# untitled.net
KiCad netlist of a schematic drawn in EAGLE
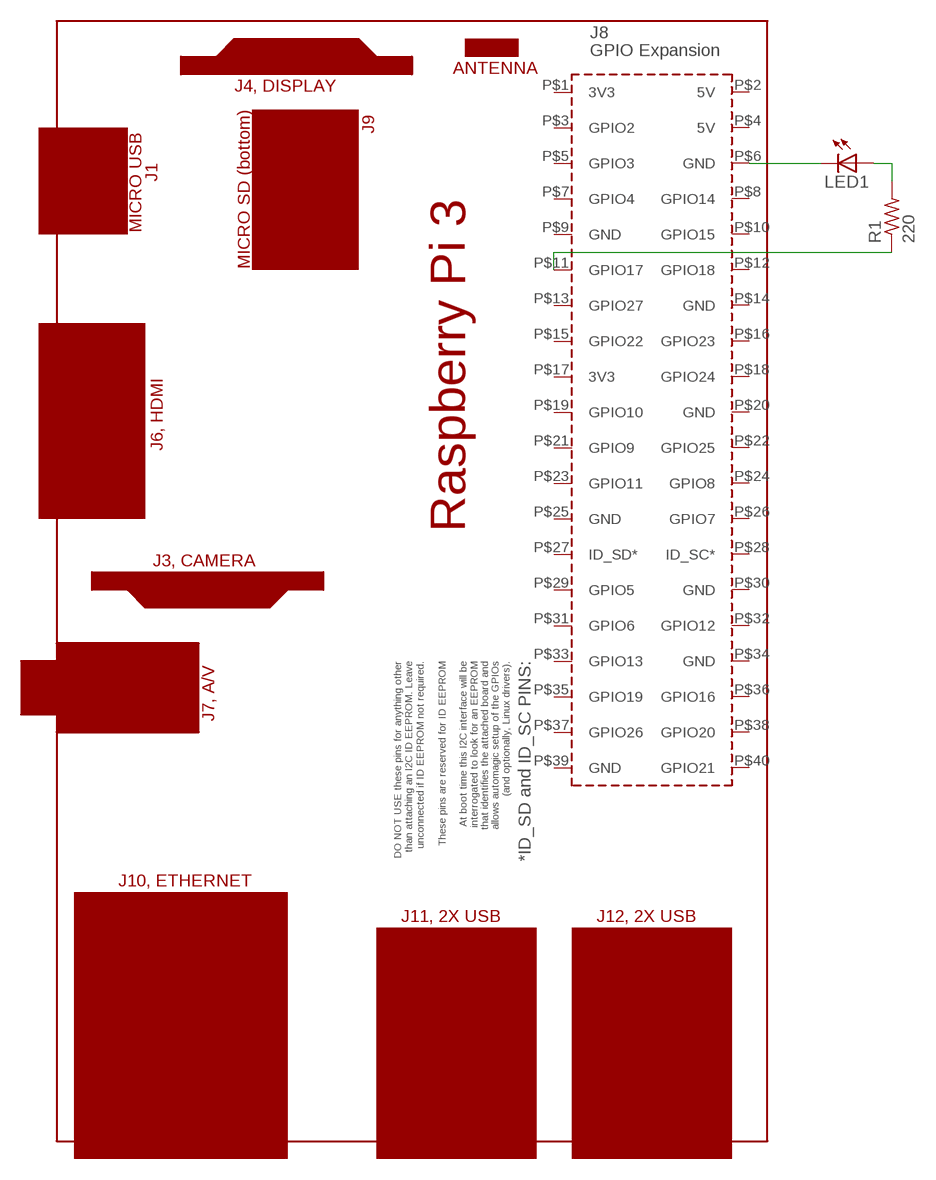
[diagram p0: schematic, sheet 1]

(export (version "E")
  (design (tool "Eeschema 10.0.6"))
  (components
    (comp (ref "LED1")
      (value "LED3MM")
      (footprint "eagle-import:LED3MM")
      (libsource (lib "eagle-import") (part "LED3MM"))
    )
    (comp (ref "PCB1")
      (value "RPI3RPI3")
      (footprint "eagle-import:RPI3")
      (libsource (lib "eagle-import") (part "RPI3RPI3"))
    )
    (comp (ref "R1")
      (value "220")
      (footprint "eagle-import:0204_7")
      (libsource (lib "eagle-import") (part "R-US_0204/7"))
    )
  )
  (nets
    (net (code "1") (name "Net-(LED1-C)") (class "Default")
      (node (ref "LED1") (pin "K") (pinfunction "C_K") (pintype "passive"))
      (node (ref "PCB1") (pin "P$6") (pinfunction "GND_P$6") (pintype "bidirectional"))
    )
    (net (code "2") (name "Net-(LED1-PadA)") (class "Default")
      (node (ref "LED1") (pin "A") (pinfunction "A_A") (pintype "passive"))
      (node (ref "R1") (pin "2") (pinfunction "2_2") (pintype "passive"))
    )
    (net (code "3") (name "Net-(PCB1-GPIO17)") (class "Default")
      (node (ref "PCB1") (pin "P$11") (pinfunction "GPIO17_P$11") (pintype "bidirectional"))
      (node (ref "R1") (pin "1") (pinfunction "1_1") (pintype "passive"))
    )
    (net (code "4") (name "unconnected-(PCB1-3V3-PadP$1)") (class "Default")
      (node (ref "PCB1") (pin "P$1") (pinfunction "3V3_P$1") (pintype "bidirectional"))
    )
    (net (code "5") (name "unconnected-(PCB1-3V3-PadP$17)") (class "Default")
      (node (ref "PCB1") (pin "P$17") (pinfunction "3V3_P$17") (pintype "bidirectional"))
    )
    (net (code "6") (name "unconnected-(PCB1-5V-PadP$2)") (class "Default")
      (node (ref "PCB1") (pin "P$2") (pinfunction "5V_P$2") (pintype "bidirectional"))
    )
    (net (code "7") (name "unconnected-(PCB1-5V-PadP$4)") (class "Default")
      (node (ref "PCB1") (pin "P$4") (pinfunction "5V_P$4") (pintype "bidirectional"))
    )
    (net (code "8") (name "unconnected-(PCB1-GND-PadP$9)") (class "Default")
      (node (ref "PCB1") (pin "P$9") (pinfunction "GND_P$9") (pintype "bidirectional"))
    )
    (net (code "9") (name "unconnected-(PCB1-GND-PadP$14)") (class "Default")
      (node (ref "PCB1") (pin "P$14") (pinfunction "GND_P$14") (pintype "bidirectional"))
    )
    (net (code "10") (name "unconnected-(PCB1-GND-PadP$20)") (class "Default")
      (node (ref "PCB1") (pin "P$20") (pinfunction "GND_P$20") (pintype "bidirectional"))
    )
    (net (code "11") (name "unconnected-(PCB1-GND-PadP$25)") (class "Default")
      (node (ref "PCB1") (pin "P$25") (pinfunction "GND_P$25") (pintype "bidirectional"))
    )
    (net (code "12") (name "unconnected-(PCB1-GND-PadP$30)") (class "Default")
      (node (ref "PCB1") (pin "P$30") (pinfunction "GND_P$30") (pintype "bidirectional"))
    )
    (net (code "13") (name "unconnected-(PCB1-GND-PadP$34)") (class "Default")
      (node (ref "PCB1") (pin "P$34") (pinfunction "GND_P$34") (pintype "bidirectional"))
    )
    (net (code "14") (name "unconnected-(PCB1-GND-PadP$39)") (class "Default")
      (node (ref "PCB1") (pin "P$39") (pinfunction "GND_P$39") (pintype "bidirectional"))
    )
    (net (code "15") (name "unconnected-(PCB1-GPIO2-PadP$3)") (class "Default")
      (node (ref "PCB1") (pin "P$3") (pinfunction "GPIO2_P$3") (pintype "bidirectional"))
    )
    (net (code "16") (name "unconnected-(PCB1-GPIO3-PadP$5)") (class "Default")
      (node (ref "PCB1") (pin "P$5") (pinfunction "GPIO3_P$5") (pintype "bidirectional"))
    )
    (net (code "17") (name "unconnected-(PCB1-GPIO4-PadP$7)") (class "Default")
      (node (ref "PCB1") (pin "P$7") (pinfunction "GPIO4_P$7") (pintype "bidirectional"))
    )
    (net (code "18") (name "unconnected-(PCB1-GPIO5-PadP$29)") (class "Default")
      (node (ref "PCB1") (pin "P$29") (pinfunction "GPIO5_P$29") (pintype "bidirectional"))
    )
    (net (code "19") (name "unconnected-(PCB1-GPIO6-PadP$31)") (class "Default")
      (node (ref "PCB1") (pin "P$31") (pinfunction "GPIO6_P$31") (pintype "bidirectional"))
    )
    (net (code "20") (name "unconnected-(PCB1-GPIO7-PadP$26)") (class "Default")
      (node (ref "PCB1") (pin "P$26") (pinfunction "GPIO7_P$26") (pintype "bidirectional"))
    )
    (net (code "21") (name "unconnected-(PCB1-GPIO8-PadP$24)") (class "Default")
      (node (ref "PCB1") (pin "P$24") (pinfunction "GPIO8_P$24") (pintype "bidirectional"))
    )
    (net (code "22") (name "unconnected-(PCB1-GPIO9-PadP$21)") (class "Default")
      (node (ref "PCB1") (pin "P$21") (pinfunction "GPIO9_P$21") (pintype "bidirectional"))
    )
    (net (code "23") (name "unconnected-(PCB1-GPIO10-PadP$19)") (class "Default")
      (node (ref "PCB1") (pin "P$19") (pinfunction "GPIO10_P$19") (pintype "bidirectional"))
    )
    (net (code "24") (name "unconnected-(PCB1-GPIO11-PadP$23)") (class "Default")
      (node (ref "PCB1") (pin "P$23") (pinfunction "GPIO11_P$23") (pintype "bidirectional"))
    )
    (net (code "25") (name "unconnected-(PCB1-GPIO12-PadP$32)") (class "Default")
      (node (ref "PCB1") (pin "P$32") (pinfunction "GPIO12_P$32") (pintype "bidirectional"))
    )
    (net (code "26") (name "unconnected-(PCB1-GPIO13-PadP$33)") (class "Default")
      (node (ref "PCB1") (pin "P$33") (pinfunction "GPIO13_P$33") (pintype "bidirectional"))
    )
    (net (code "27") (name "unconnected-(PCB1-GPIO14-PadP$8)") (class "Default")
      (node (ref "PCB1") (pin "P$8") (pinfunction "GPIO14_P$8") (pintype "bidirectional"))
    )
    (net (code "28") (name "unconnected-(PCB1-GPIO15-PadP$10)") (class "Default")
      (node (ref "PCB1") (pin "P$10") (pinfunction "GPIO15_P$10") (pintype "bidirectional"))
    )
    (net (code "29") (name "unconnected-(PCB1-GPIO16-PadP$36)") (class "Default")
      (node (ref "PCB1") (pin "P$36") (pinfunction "GPIO16_P$36") (pintype "bidirectional"))
    )
    (net (code "30") (name "unconnected-(PCB1-GPIO18-PadP$12)") (class "Default")
      (node (ref "PCB1") (pin "P$12") (pinfunction "GPIO18_P$12") (pintype "bidirectional"))
    )
    (net (code "31") (name "unconnected-(PCB1-GPIO19-PadP$35)") (class "Default")
      (node (ref "PCB1") (pin "P$35") (pinfunction "GPIO19_P$35") (pintype "bidirectional"))
    )
    (net (code "32") (name "unconnected-(PCB1-GPIO20-PadP$38)") (class "Default")
      (node (ref "PCB1") (pin "P$38") (pinfunction "GPIO20_P$38") (pintype "bidirectional"))
    )
    (net (code "33") (name "unconnected-(PCB1-GPIO21-PadP$40)") (class "Default")
      (node (ref "PCB1") (pin "P$40") (pinfunction "GPIO21_P$40") (pintype "bidirectional"))
    )
    (net (code "34") (name "unconnected-(PCB1-GPIO22-PadP$15)") (class "Default")
      (node (ref "PCB1") (pin "P$15") (pinfunction "GPIO22_P$15") (pintype "bidirectional"))
    )
    (net (code "35") (name "unconnected-(PCB1-GPIO23-PadP$16)") (class "Default")
      (node (ref "PCB1") (pin "P$16") (pinfunction "GPIO23_P$16") (pintype "bidirectional"))
    )
    (net (code "36") (name "unconnected-(PCB1-GPIO24-PadP$18)") (class "Default")
      (node (ref "PCB1") (pin "P$18") (pinfunction "GPIO24_P$18") (pintype "bidirectional"))
    )
    (net (code "37") (name "unconnected-(PCB1-GPIO25-PadP$22)") (class "Default")
      (node (ref "PCB1") (pin "P$22") (pinfunction "GPIO25_P$22") (pintype "bidirectional"))
    )
    (net (code "38") (name "unconnected-(PCB1-GPIO26-PadP$37)") (class "Default")
      (node (ref "PCB1") (pin "P$37") (pinfunction "GPIO26_P$37") (pintype "bidirectional"))
    )
    (net (code "39") (name "unconnected-(PCB1-GPIO27-PadP$13)") (class "Default")
      (node (ref "PCB1") (pin "P$13") (pinfunction "GPIO27_P$13") (pintype "bidirectional"))
    )
    (net (code "40") (name "unconnected-(PCB1-ID_SC*-PadP$28)") (class "Default")
      (node (ref "PCB1") (pin "P$28") (pinfunction "ID_SC*_P$28") (pintype "bidirectional"))
    )
    (net (code "41") (name "unconnected-(PCB1-ID_SD*-PadP$27)") (class "Default")
      (node (ref "PCB1") (pin "P$27") (pinfunction "ID_SD*_P$27") (pintype "bidirectional"))
    )
  )
)
